# Op_Amp_VU_Meter_3_Led.net
KiCad netlist of a schematic drawn in EAGLE
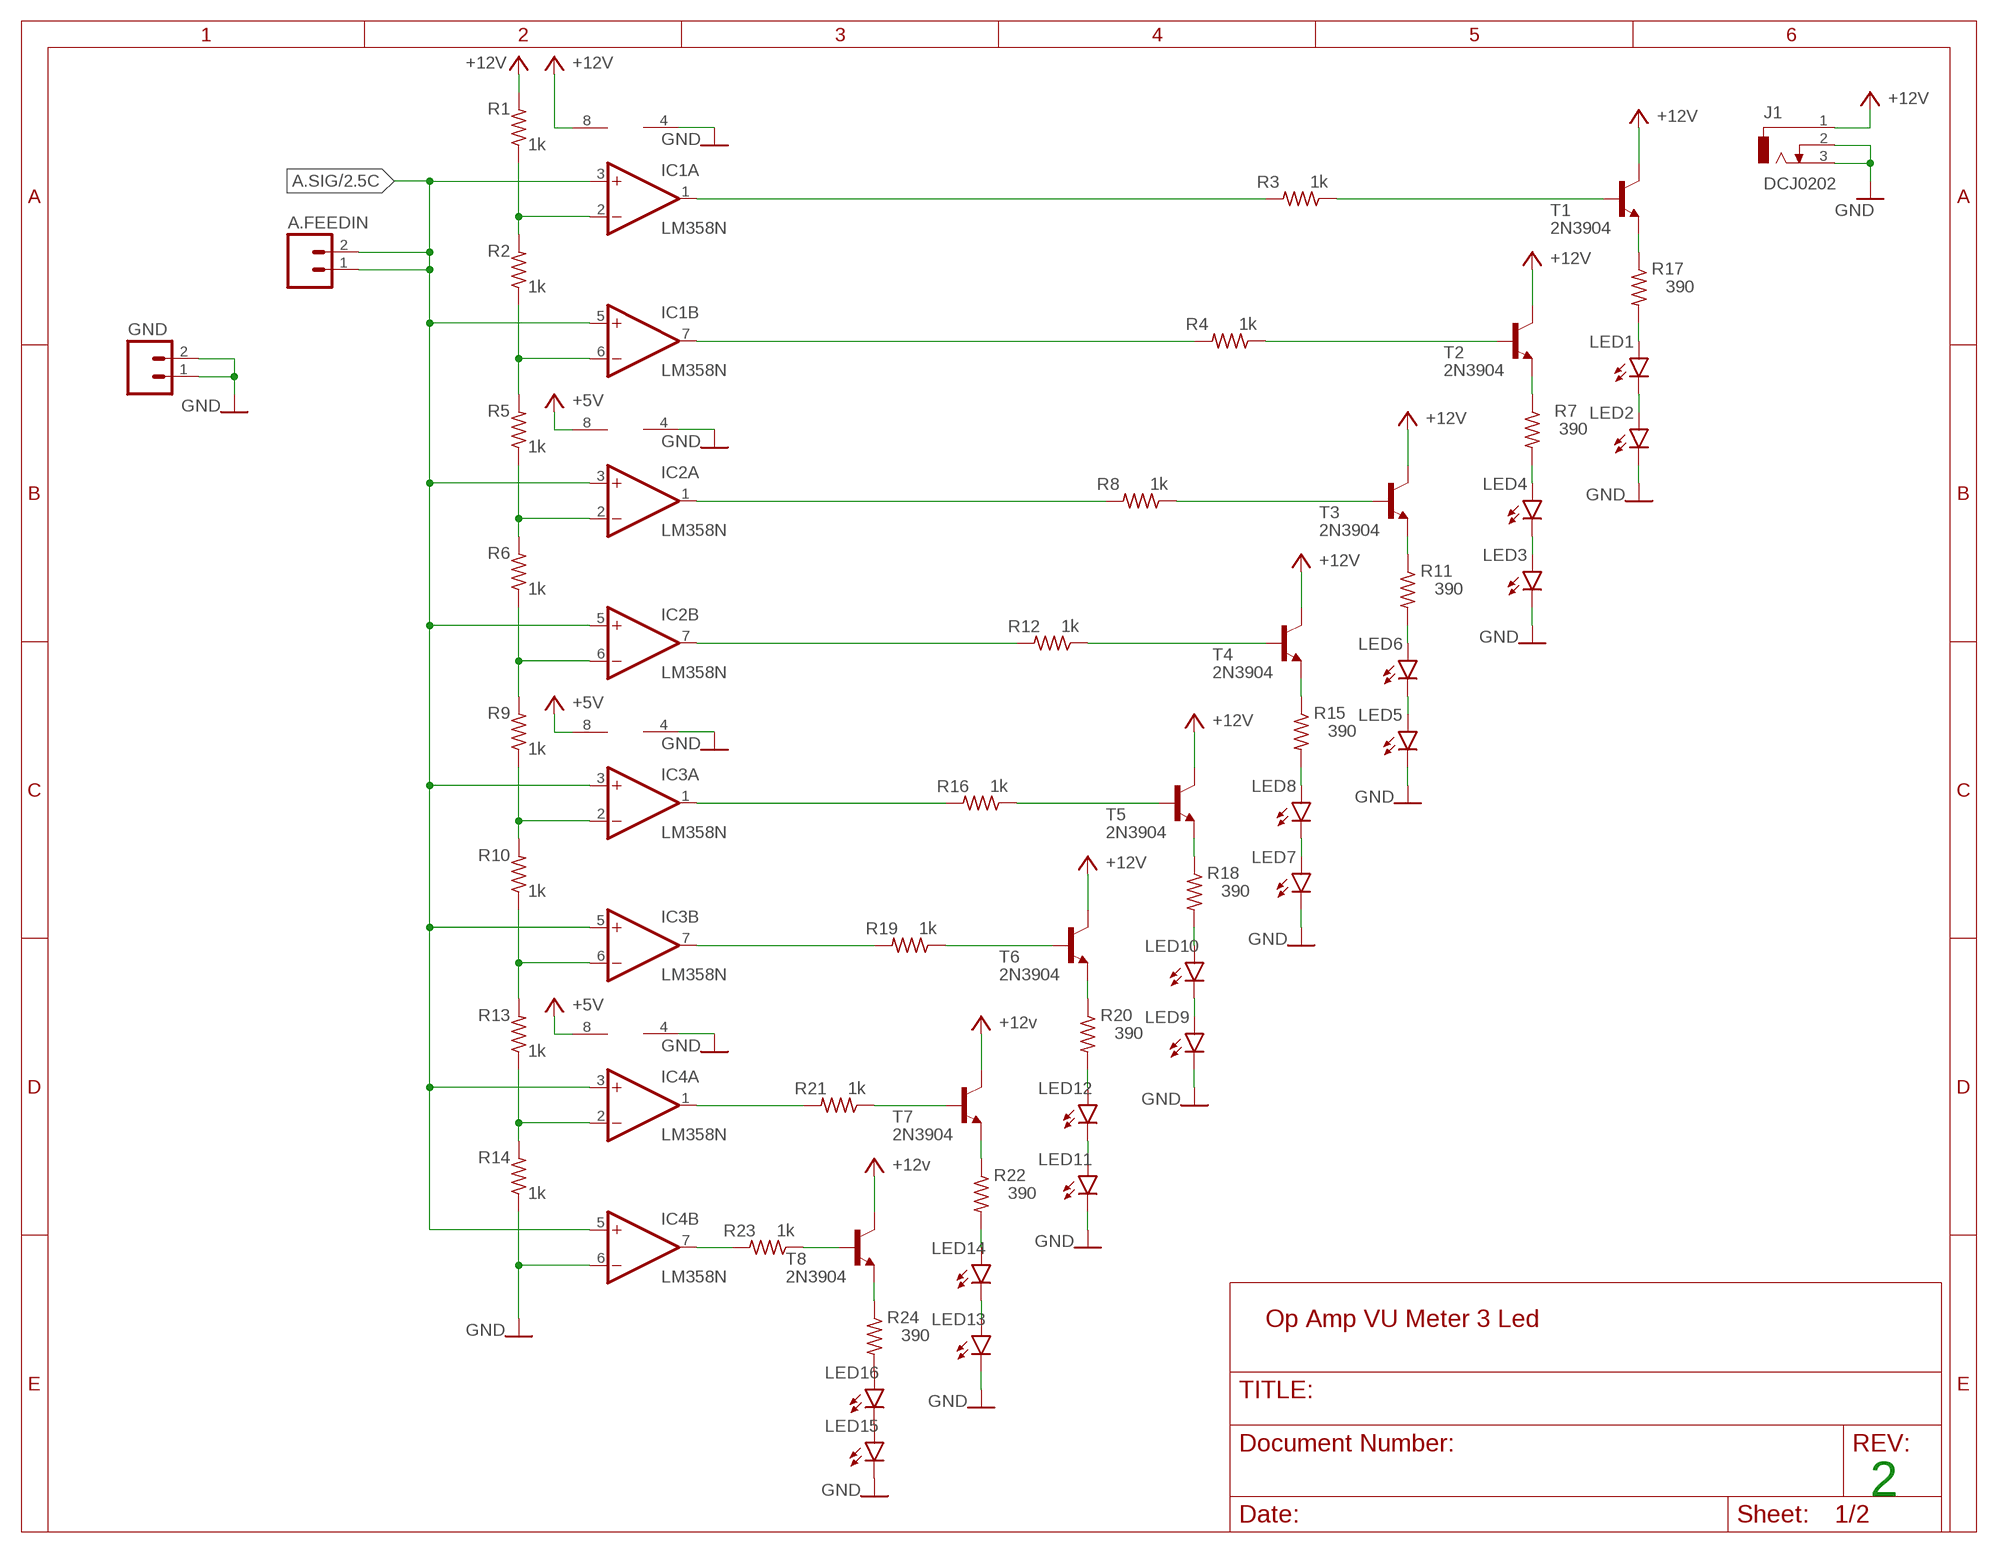
[diagram p0: schematic, sheet 1]
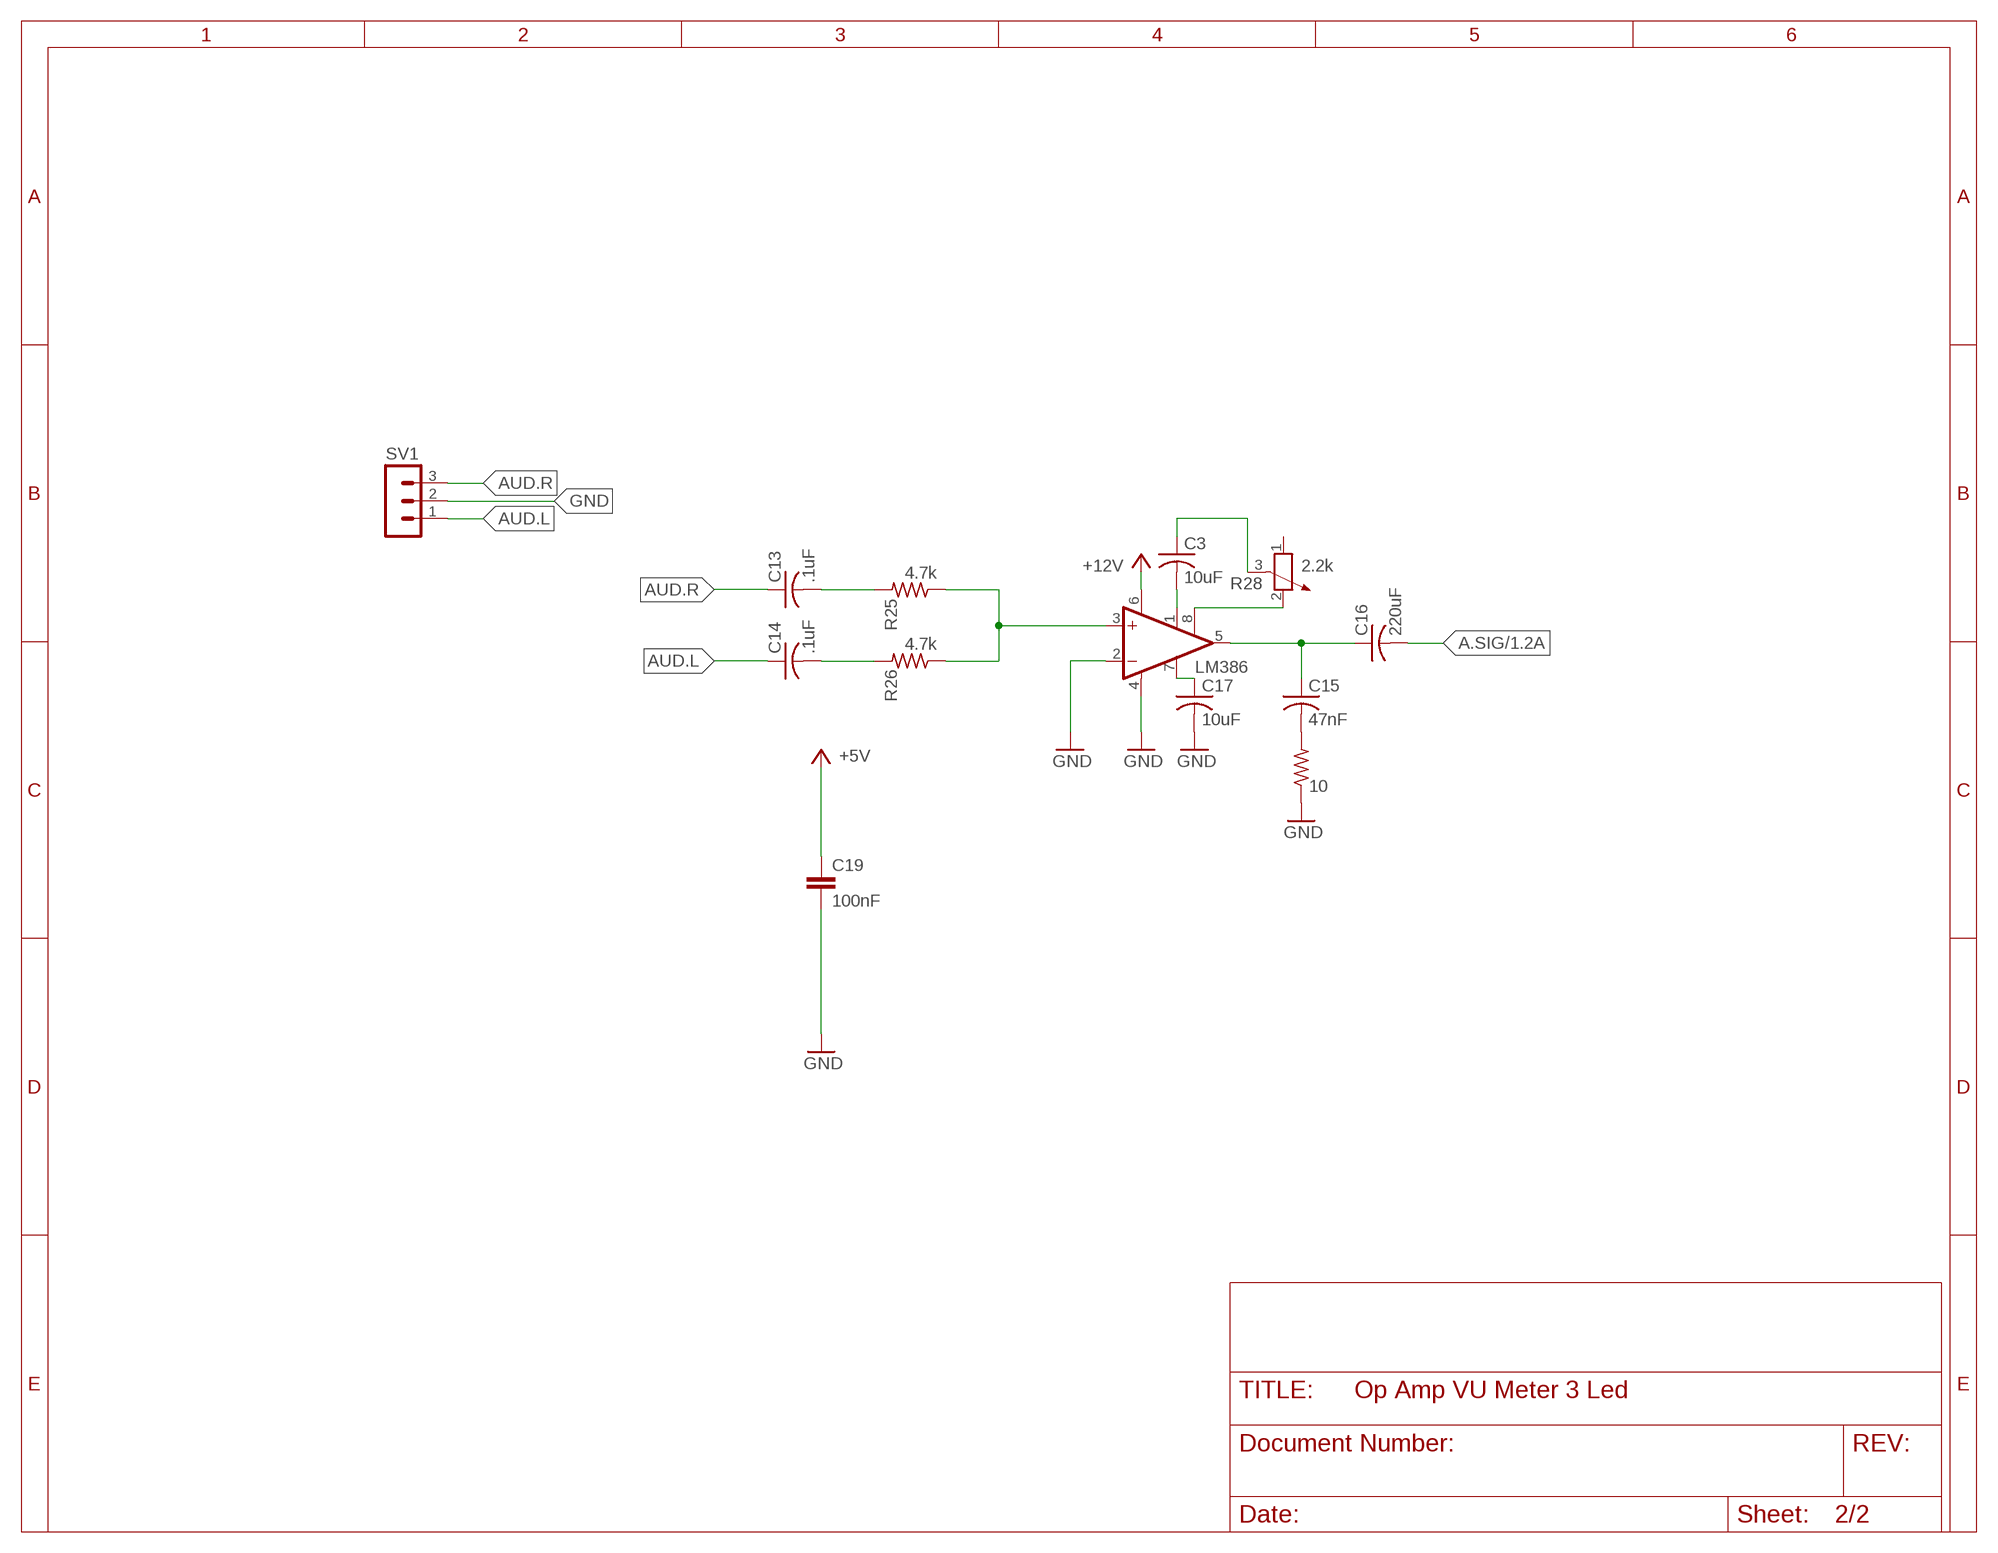
[diagram p1: schematic, sheet 2]

(export (version "E")
  (design (tool "Eeschema 10.0.6"))
  (components
    (comp (ref "C3")
      (value "10uF")
      (footprint "eagle-import:C050-024X044")
      (libsource (lib "eagle-import") (part "C-US050-024X044"))
    )
    (comp (ref "C13")
      (value ".1uF")
      (footprint "eagle-import:C050-024X044")
      (libsource (lib "eagle-import") (part "C-US050-024X044"))
    )
    (comp (ref "C14")
      (value ".1uF")
      (footprint "eagle-import:C050-024X044")
      (libsource (lib "eagle-import") (part "C-US050-024X044"))
    )
    (comp (ref "C15")
      (value "47nF")
      (footprint "eagle-import:C050-024X044")
      (libsource (lib "eagle-import") (part "C-US050-024X044"))
    )
    (comp (ref "C16")
      (value "220uF")
      (footprint "eagle-import:C050-024X044")
      (libsource (lib "eagle-import") (part "C-US050-024X044"))
    )
    (comp (ref "C17")
      (value "10uF")
      (footprint "eagle-import:C050-024X044")
      (libsource (lib "eagle-import") (part "C-US050-024X044"))
    )
    (comp (ref "C19")
      (value "100nF")
      (footprint "eagle-import:C025-025X050")
      (libsource (lib "eagle-import") (part "C-EU025-025X050"))
    )
    (comp (ref "LM386")
      (value "LM386N-1")
      (footprint "eagle-import:DIL08")
      (libsource (lib "eagle-import") (part "LM386?-N1"))
    )
    (comp (ref "R25")
      (value "4.7k")
      (footprint "eagle-import:0207_12")
      (libsource (lib "eagle-import") (part "R-US_0207/12"))
    )
    (comp (ref "R26")
      (value "4.7k")
      (footprint "eagle-import:0207_12")
      (libsource (lib "eagle-import") (part "R-US_0207/12"))
    )
    (comp (ref "R27")
      (value "10")
      (footprint "eagle-import:0207_12")
      (libsource (lib "eagle-import") (part "R-US_0207/12"))
    )
    (comp (ref "R28")
      (value "2.2k")
      (footprint "eagle-import:PT-10S")
      (libsource (lib "eagle-import") (part "POTENTIOMETER_PT-10S"))
    )
    (comp (ref "SV1")
      (value "MA03-1")
      (footprint "eagle-import:MA03-1")
      (libsource (lib "eagle-import") (part "MA03-1"))
    )
    (comp (ref "A.FEEDIN")
      (value "MA02")
      (footprint "eagle-import:02PA")
      (libsource (lib "eagle-import") (part "MA02"))
    )
    (comp (ref "GND")
      (value "MA02")
      (footprint "eagle-import:02PA")
      (libsource (lib "eagle-import") (part "MA02"))
    )
    (comp (ref "IC1")
      (value "LM358N")
      (footprint "eagle-import:DIL08")
      (libsource (lib "eagle-import") (part "LM358N"))
    )
    (comp (ref "IC2")
      (value "LM358N")
      (footprint "eagle-import:DIL08")
      (libsource (lib "eagle-import") (part "LM358N"))
    )
    (comp (ref "IC3")
      (value "LM358N")
      (footprint "eagle-import:DIL08")
      (libsource (lib "eagle-import") (part "LM358N"))
    )
    (comp (ref "IC4")
      (value "LM358N")
      (footprint "eagle-import:DIL08")
      (libsource (lib "eagle-import") (part "LM358N"))
    )
    (comp (ref "J1")
      (value "DCJ0202")
      (footprint "eagle-import:DCJ0202")
      (libsource (lib "eagle-import") (part "DCJ0202"))
    )
    (comp (ref "LED1")
      (value "LED5MM")
      (footprint "eagle-import:LED5MM")
      (libsource (lib "eagle-import") (part "LED5MM"))
    )
    (comp (ref "LED2")
      (value "LED5MM")
      (footprint "eagle-import:LED5MM")
      (libsource (lib "eagle-import") (part "LED5MM"))
    )
    (comp (ref "LED3")
      (value "LED5MM")
      (footprint "eagle-import:LED5MM")
      (libsource (lib "eagle-import") (part "LED5MM"))
    )
    (comp (ref "LED4")
      (value "LED5MM")
      (footprint "eagle-import:LED5MM")
      (libsource (lib "eagle-import") (part "LED5MM"))
    )
    (comp (ref "LED5")
      (value "LED5MM")
      (footprint "eagle-import:LED5MM")
      (libsource (lib "eagle-import") (part "LED5MM"))
    )
    (comp (ref "LED6")
      (value "LED5MM")
      (footprint "eagle-import:LED5MM")
      (libsource (lib "eagle-import") (part "LED5MM"))
    )
    (comp (ref "LED7")
      (value "LED5MM")
      (footprint "eagle-import:LED5MM")
      (libsource (lib "eagle-import") (part "LED5MM"))
    )
    (comp (ref "LED8")
      (value "LED5MM")
      (footprint "eagle-import:LED5MM")
      (libsource (lib "eagle-import") (part "LED5MM"))
    )
    (comp (ref "LED9")
      (value "LED5MM")
      (footprint "eagle-import:LED5MM")
      (libsource (lib "eagle-import") (part "LED5MM"))
    )
    (comp (ref "LED10")
      (value "LED5MM")
      (footprint "eagle-import:LED5MM")
      (libsource (lib "eagle-import") (part "LED5MM"))
    )
    (comp (ref "LED11")
      (value "LED5MM")
      (footprint "eagle-import:LED5MM")
      (libsource (lib "eagle-import") (part "LED5MM"))
    )
    (comp (ref "LED12")
      (value "LED5MM")
      (footprint "eagle-import:LED5MM")
      (libsource (lib "eagle-import") (part "LED5MM"))
    )
    (comp (ref "LED13")
      (value "LED5MM")
      (footprint "eagle-import:LED5MM")
      (libsource (lib "eagle-import") (part "LED5MM"))
    )
    (comp (ref "LED14")
      (value "LED5MM")
      (footprint "eagle-import:LED5MM")
      (libsource (lib "eagle-import") (part "LED5MM"))
    )
    (comp (ref "LED15")
      (value "LED5MM")
      (footprint "eagle-import:LED5MM")
      (libsource (lib "eagle-import") (part "LED5MM"))
    )
    (comp (ref "LED16")
      (value "LED5MM")
      (footprint "eagle-import:LED5MM")
      (libsource (lib "eagle-import") (part "LED5MM"))
    )
    (comp (ref "R1")
      (value "1k")
      (footprint "eagle-import:0207_12")
      (libsource (lib "eagle-import") (part "R-US_0207/12"))
    )
    (comp (ref "R2")
      (value "1k")
      (footprint "eagle-import:0207_12")
      (libsource (lib "eagle-import") (part "R-US_0207/12"))
    )
    (comp (ref "R3")
      (value "1k")
      (footprint "eagle-import:0207_12")
      (libsource (lib "eagle-import") (part "R-US_0207/12"))
    )
    (comp (ref "R4")
      (value "1k")
      (footprint "eagle-import:0207_12")
      (libsource (lib "eagle-import") (part "R-US_0207/12"))
    )
    (comp (ref "R5")
      (value "1k")
      (footprint "eagle-import:0207_12")
      (libsource (lib "eagle-import") (part "R-US_0207/12"))
    )
    (comp (ref "R6")
      (value "1k")
      (footprint "eagle-import:0207_12")
      (libsource (lib "eagle-import") (part "R-US_0207/12"))
    )
    (comp (ref "R7")
      (value "390")
      (footprint "eagle-import:0207_12")
      (libsource (lib "eagle-import") (part "R-US_0207/12"))
    )
    (comp (ref "R8")
      (value "1k")
      (footprint "eagle-import:0207_12")
      (libsource (lib "eagle-import") (part "R-US_0207/12"))
    )
    (comp (ref "R9")
      (value "1k")
      (footprint "eagle-import:0207_12")
      (libsource (lib "eagle-import") (part "R-US_0207/12"))
    )
    (comp (ref "R10")
      (value "1k")
      (footprint "eagle-import:0207_12")
      (libsource (lib "eagle-import") (part "R-US_0207/12"))
    )
    (comp (ref "R11")
      (value "390")
      (footprint "eagle-import:0207_12")
      (libsource (lib "eagle-import") (part "R-US_0207/12"))
    )
    (comp (ref "R12")
      (value "1k")
      (footprint "eagle-import:0207_12")
      (libsource (lib "eagle-import") (part "R-US_0207/12"))
    )
    (comp (ref "R13")
      (value "1k")
      (footprint "eagle-import:0207_12")
      (libsource (lib "eagle-import") (part "R-US_0207/12"))
    )
    (comp (ref "R14")
      (value "1k")
      (footprint "eagle-import:0207_12")
      (libsource (lib "eagle-import") (part "R-US_0207/12"))
    )
    (comp (ref "R15")
      (value "390")
      (footprint "eagle-import:0207_12")
      (libsource (lib "eagle-import") (part "R-US_0207/12"))
    )
    (comp (ref "R16")
      (value "1k")
      (footprint "eagle-import:0207_12")
      (libsource (lib "eagle-import") (part "R-US_0207/12"))
    )
    (comp (ref "R17")
      (value "390")
      (footprint "eagle-import:0207_12")
      (libsource (lib "eagle-import") (part "R-US_0207/12"))
    )
    (comp (ref "R18")
      (value "390")
      (footprint "eagle-import:0207_12")
      (libsource (lib "eagle-import") (part "R-US_0207/12"))
    )
    (comp (ref "R19")
      (value "1k")
      (footprint "eagle-import:0207_12")
      (libsource (lib "eagle-import") (part "R-US_0207/12"))
    )
    (comp (ref "R20")
      (value "390")
      (footprint "eagle-import:0207_12")
      (libsource (lib "eagle-import") (part "R-US_0207/12"))
    )
    (comp (ref "R21")
      (value "1k")
      (footprint "eagle-import:0207_12")
      (libsource (lib "eagle-import") (part "R-US_0207/12"))
    )
    (comp (ref "R22")
      (value "390")
      (footprint "eagle-import:0207_12")
      (libsource (lib "eagle-import") (part "R-US_0207/12"))
    )
    (comp (ref "R23")
      (value "1k")
      (footprint "eagle-import:0207_12")
      (libsource (lib "eagle-import") (part "R-US_0207/12"))
    )
    (comp (ref "R24")
      (value "390")
      (footprint "eagle-import:0207_12")
      (libsource (lib "eagle-import") (part "R-US_0207/12"))
    )
    (comp (ref "T1")
      (value "2N3904")
      (footprint "eagle-import:TO92")
      (libsource (lib "eagle-import") (part "2N3904"))
    )
    (comp (ref "T2")
      (value "2N3904")
      (footprint "eagle-import:TO92")
      (libsource (lib "eagle-import") (part "2N3904"))
    )
    (comp (ref "T3")
      (value "2N3904")
      (footprint "eagle-import:TO92")
      (libsource (lib "eagle-import") (part "2N3904"))
    )
    (comp (ref "T4")
      (value "2N3904")
      (footprint "eagle-import:TO92")
      (libsource (lib "eagle-import") (part "2N3904"))
    )
    (comp (ref "T5")
      (value "2N3904")
      (footprint "eagle-import:TO92")
      (libsource (lib "eagle-import") (part "2N3904"))
    )
    (comp (ref "T6")
      (value "2N3904")
      (footprint "eagle-import:TO92")
      (libsource (lib "eagle-import") (part "2N3904"))
    )
    (comp (ref "T7")
      (value "2N3904")
      (footprint "eagle-import:TO92")
      (libsource (lib "eagle-import") (part "2N3904"))
    )
    (comp (ref "T8")
      (value "2N3904")
      (footprint "eagle-import:TO92")
      (libsource (lib "eagle-import") (part "2N3904"))
    )
  )
  (nets
    (net (code "1") (name "+5V") (class "Default")
      (node (ref "C19") (pin "1") (pinfunction "1_1") (pintype "passive"))
      (node (ref "IC1") (pin "8") (pinfunction "V+_8") (pintype "power_in"))
      (node (ref "IC2") (pin "8") (pinfunction "V+_8") (pintype "power_in"))
      (node (ref "IC3") (pin "8") (pinfunction "V+_8") (pintype "power_in"))
      (node (ref "IC4") (pin "8") (pinfunction "V+_8") (pintype "power_in"))
      (node (ref "J1") (pin "1") (pinfunction "1_1") (pintype "passive"))
      (node (ref "LM386") (pin "6") (pinfunction "VS_6") (pintype "power_in"))
      (node (ref "R1") (pin "2") (pinfunction "2_2") (pintype "passive"))
      (node (ref "T1") (pin "1") (pinfunction "C_1") (pintype "passive"))
      (node (ref "T2") (pin "1") (pinfunction "C_1") (pintype "passive"))
      (node (ref "T3") (pin "1") (pinfunction "C_1") (pintype "passive"))
      (node (ref "T4") (pin "1") (pinfunction "C_1") (pintype "passive"))
      (node (ref "T5") (pin "1") (pinfunction "C_1") (pintype "passive"))
      (node (ref "T6") (pin "1") (pinfunction "C_1") (pintype "passive"))
      (node (ref "T7") (pin "1") (pinfunction "C_1") (pintype "passive"))
      (node (ref "T8") (pin "1") (pinfunction "C_1") (pintype "passive"))
    )
    (net (code "2") (name "A.SIG") (class "Default")
      (node (ref "A.FEEDIN") (pin "1") (pinfunction "1_1") (pintype "passive"))
      (node (ref "A.FEEDIN") (pin "2") (pinfunction "2_2") (pintype "passive"))
      (node (ref "C16") (pin "2") (pinfunction "2_2") (pintype "passive"))
      (node (ref "IC1") (pin "3") (pinfunction "+IN_3") (pintype "input"))
      (node (ref "IC1") (pin "5") (pinfunction "+IN_5") (pintype "input"))
      (node (ref "IC2") (pin "3") (pinfunction "+IN_3") (pintype "input"))
      (node (ref "IC2") (pin "5") (pinfunction "+IN_5") (pintype "input"))
      (node (ref "IC3") (pin "3") (pinfunction "+IN_3") (pintype "input"))
      (node (ref "IC3") (pin "5") (pinfunction "+IN_5") (pintype "input"))
      (node (ref "IC4") (pin "3") (pinfunction "+IN_3") (pintype "input"))
      (node (ref "IC4") (pin "5") (pinfunction "+IN_5") (pintype "input"))
    )
    (net (code "3") (name "AUD.L") (class "Default")
      (node (ref "C14") (pin "1") (pinfunction "1_1") (pintype "passive"))
      (node (ref "SV1") (pin "1") (pinfunction "1_1") (pintype "passive"))
    )
    (net (code "4") (name "AUD.R") (class "Default")
      (node (ref "C13") (pin "1") (pinfunction "1_1") (pintype "passive"))
      (node (ref "SV1") (pin "3") (pinfunction "3_3") (pintype "passive"))
    )
    (net (code "5") (name "GND") (class "Default")
      (node (ref "C17") (pin "2") (pinfunction "2_2") (pintype "passive"))
      (node (ref "C19") (pin "2") (pinfunction "2_2") (pintype "passive"))
      (node (ref "GND") (pin "1") (pinfunction "1_1") (pintype "passive"))
      (node (ref "GND") (pin "2") (pinfunction "2_2") (pintype "passive"))
      (node (ref "IC1") (pin "4") (pinfunction "V-_4") (pintype "power_in"))
      (node (ref "IC2") (pin "4") (pinfunction "V-_4") (pintype "power_in"))
      (node (ref "IC3") (pin "4") (pinfunction "V-_4") (pintype "power_in"))
      (node (ref "IC4") (pin "4") (pinfunction "V-_4") (pintype "power_in"))
      (node (ref "IC4") (pin "6") (pinfunction "-IN_6") (pintype "input"))
      (node (ref "J1") (pin "2") (pinfunction "2_2") (pintype "passive"))
      (node (ref "J1") (pin "3") (pinfunction "3_3") (pintype "passive"))
      (node (ref "LED11") (pin "K") (pinfunction "C_K") (pintype "passive"))
      (node (ref "LED13") (pin "K") (pinfunction "C_K") (pintype "passive"))
      (node (ref "LED15") (pin "K") (pinfunction "C_K") (pintype "passive"))
      (node (ref "LED2") (pin "K") (pinfunction "C_K") (pintype "passive"))
      (node (ref "LED3") (pin "K") (pinfunction "C_K") (pintype "passive"))
      (node (ref "LED5") (pin "K") (pinfunction "C_K") (pintype "passive"))
      (node (ref "LED7") (pin "K") (pinfunction "C_K") (pintype "passive"))
      (node (ref "LED9") (pin "K") (pinfunction "C_K") (pintype "passive"))
      (node (ref "LM386") (pin "2") (pinfunction "-IN_2") (pintype "input"))
      (node (ref "LM386") (pin "4") (pinfunction "GND_4") (pintype "power_in"))
      (node (ref "R14") (pin "1") (pinfunction "1_1") (pintype "passive"))
      (node (ref "R27") (pin "1") (pinfunction "1_1") (pintype "passive"))
      (node (ref "SV1") (pin "2") (pinfunction "2_2") (pintype "passive"))
    )
    (net (code "6") (name "Net-(C3-Pad1)") (class "Default")
      (node (ref "C3") (pin "1") (pinfunction "1_1") (pintype "passive"))
      (node (ref "R28") (pin "3") (pinfunction "3_3") (pintype "passive"))
    )
    (net (code "7") (name "Net-(C3-Pad2)") (class "Default")
      (node (ref "C3") (pin "2") (pinfunction "2_2") (pintype "passive"))
      (node (ref "LM386") (pin "1") (pinfunction "GAIN_1") (pintype "passive"))
    )
    (net (code "8") (name "Net-(C13-Pad2)") (class "Default")
      (node (ref "C13") (pin "2") (pinfunction "2_2") (pintype "passive"))
      (node (ref "R25") (pin "2") (pinfunction "2_2") (pintype "passive"))
    )
    (net (code "9") (name "Net-(C14-Pad2)") (class "Default")
      (node (ref "C14") (pin "2") (pinfunction "2_2") (pintype "passive"))
      (node (ref "R26") (pin "2") (pinfunction "2_2") (pintype "passive"))
    )
    (net (code "10") (name "Net-(C15-Pad2)") (class "Default")
      (node (ref "C15") (pin "2") (pinfunction "2_2") (pintype "passive"))
      (node (ref "R27") (pin "2") (pinfunction "2_2") (pintype "passive"))
    )
    (net (code "11") (name "Net-(IC1A--IN)") (class "Default")
      (node (ref "IC1") (pin "2") (pinfunction "-IN_2") (pintype "input"))
      (node (ref "R1") (pin "1") (pinfunction "1_1") (pintype "passive"))
      (node (ref "R2") (pin "2") (pinfunction "2_2") (pintype "passive"))
    )
    (net (code "12") (name "Net-(IC1A-OUT)") (class "Default")
      (node (ref "IC1") (pin "1") (pinfunction "OUT_1") (pintype "output"))
      (node (ref "R3") (pin "2") (pinfunction "2_2") (pintype "passive"))
    )
    (net (code "13") (name "Net-(IC1B--IN)") (class "Default")
      (node (ref "IC1") (pin "6") (pinfunction "-IN_6") (pintype "input"))
      (node (ref "R2") (pin "1") (pinfunction "1_1") (pintype "passive"))
      (node (ref "R5") (pin "2") (pinfunction "2_2") (pintype "passive"))
    )
    (net (code "14") (name "Net-(IC1B-OUT)") (class "Default")
      (node (ref "IC1") (pin "7") (pinfunction "OUT_7") (pintype "output"))
      (node (ref "R4") (pin "2") (pinfunction "2_2") (pintype "passive"))
    )
    (net (code "15") (name "Net-(IC2A--IN)") (class "Default")
      (node (ref "IC2") (pin "2") (pinfunction "-IN_2") (pintype "input"))
      (node (ref "R5") (pin "1") (pinfunction "1_1") (pintype "passive"))
      (node (ref "R6") (pin "2") (pinfunction "2_2") (pintype "passive"))
    )
    (net (code "16") (name "Net-(IC2A-OUT)") (class "Default")
      (node (ref "IC2") (pin "1") (pinfunction "OUT_1") (pintype "output"))
      (node (ref "R8") (pin "2") (pinfunction "2_2") (pintype "passive"))
    )
    (net (code "17") (name "Net-(IC2B--IN)") (class "Default")
      (node (ref "IC2") (pin "6") (pinfunction "-IN_6") (pintype "input"))
      (node (ref "R6") (pin "1") (pinfunction "1_1") (pintype "passive"))
      (node (ref "R9") (pin "2") (pinfunction "2_2") (pintype "passive"))
    )
    (net (code "18") (name "Net-(IC2B-OUT)") (class "Default")
      (node (ref "IC2") (pin "7") (pinfunction "OUT_7") (pintype "output"))
      (node (ref "R12") (pin "2") (pinfunction "2_2") (pintype "passive"))
    )
    (net (code "19") (name "Net-(IC3A--IN)") (class "Default")
      (node (ref "IC3") (pin "2") (pinfunction "-IN_2") (pintype "input"))
      (node (ref "R10") (pin "2") (pinfunction "2_2") (pintype "passive"))
      (node (ref "R9") (pin "1") (pinfunction "1_1") (pintype "passive"))
    )
    (net (code "20") (name "Net-(IC3A-OUT)") (class "Default")
      (node (ref "IC3") (pin "1") (pinfunction "OUT_1") (pintype "output"))
      (node (ref "R16") (pin "2") (pinfunction "2_2") (pintype "passive"))
    )
    (net (code "21") (name "Net-(IC3B--IN)") (class "Default")
      (node (ref "IC3") (pin "6") (pinfunction "-IN_6") (pintype "input"))
      (node (ref "R10") (pin "1") (pinfunction "1_1") (pintype "passive"))
      (node (ref "R13") (pin "2") (pinfunction "2_2") (pintype "passive"))
    )
    (net (code "22") (name "Net-(IC3B-OUT)") (class "Default")
      (node (ref "IC3") (pin "7") (pinfunction "OUT_7") (pintype "output"))
      (node (ref "R19") (pin "2") (pinfunction "2_2") (pintype "passive"))
    )
    (net (code "23") (name "Net-(IC4A--IN)") (class "Default")
      (node (ref "IC4") (pin "2") (pinfunction "-IN_2") (pintype "input"))
      (node (ref "R13") (pin "1") (pinfunction "1_1") (pintype "passive"))
      (node (ref "R14") (pin "2") (pinfunction "2_2") (pintype "passive"))
    )
    (net (code "24") (name "Net-(IC4A-OUT)") (class "Default")
      (node (ref "IC4") (pin "1") (pinfunction "OUT_1") (pintype "output"))
      (node (ref "R21") (pin "2") (pinfunction "2_2") (pintype "passive"))
    )
    (net (code "25") (name "Net-(IC4B-OUT)") (class "Default")
      (node (ref "IC4") (pin "7") (pinfunction "OUT_7") (pintype "output"))
      (node (ref "R23") (pin "2") (pinfunction "2_2") (pintype "passive"))
    )
    (net (code "26") (name "Net-(LED1-C)") (class "Default")
      (node (ref "LED1") (pin "K") (pinfunction "C_K") (pintype "passive"))
      (node (ref "LED2") (pin "A") (pinfunction "A_A") (pintype "passive"))
    )
    (net (code "27") (name "Net-(LED1-PadA)") (class "Default")
      (node (ref "LED1") (pin "A") (pinfunction "A_A") (pintype "passive"))
      (node (ref "R17") (pin "2") (pinfunction "2_2") (pintype "passive"))
    )
    (net (code "28") (name "Net-(LED4-C)") (class "Default")
      (node (ref "LED3") (pin "A") (pinfunction "A_A") (pintype "passive"))
      (node (ref "LED4") (pin "K") (pinfunction "C_K") (pintype "passive"))
    )
    (net (code "29") (name "Net-(LED4-PadA)") (class "Default")
      (node (ref "LED4") (pin "A") (pinfunction "A_A") (pintype "passive"))
      (node (ref "R7") (pin "2") (pinfunction "2_2") (pintype "passive"))
    )
    (net (code "30") (name "Net-(LED6-C)") (class "Default")
      (node (ref "LED5") (pin "A") (pinfunction "A_A") (pintype "passive"))
      (node (ref "LED6") (pin "K") (pinfunction "C_K") (pintype "passive"))
    )
    (net (code "31") (name "Net-(LED6-PadA)") (class "Default")
      (node (ref "LED6") (pin "A") (pinfunction "A_A") (pintype "passive"))
      (node (ref "R11") (pin "2") (pinfunction "2_2") (pintype "passive"))
    )
    (net (code "32") (name "Net-(LED8-C)") (class "Default")
      (node (ref "LED7") (pin "A") (pinfunction "A_A") (pintype "passive"))
      (node (ref "LED8") (pin "K") (pinfunction "C_K") (pintype "passive"))
    )
    (net (code "33") (name "Net-(LED8-PadA)") (class "Default")
      (node (ref "LED8") (pin "A") (pinfunction "A_A") (pintype "passive"))
      (node (ref "R15") (pin "2") (pinfunction "2_2") (pintype "passive"))
    )
    (net (code "34") (name "Net-(LED10-C)") (class "Default")
      (node (ref "LED10") (pin "K") (pinfunction "C_K") (pintype "passive"))
      (node (ref "LED9") (pin "A") (pinfunction "A_A") (pintype "passive"))
    )
    (net (code "35") (name "Net-(LED10-PadA)") (class "Default")
      (node (ref "LED10") (pin "A") (pinfunction "A_A") (pintype "passive"))
      (node (ref "R18") (pin "2") (pinfunction "2_2") (pintype "passive"))
    )
    (net (code "36") (name "Net-(LED12-C)") (class "Default")
      (node (ref "LED11") (pin "A") (pinfunction "A_A") (pintype "passive"))
      (node (ref "LED12") (pin "K") (pinfunction "C_K") (pintype "passive"))
    )
    (net (code "37") (name "Net-(LED12-PadA)") (class "Default")
      (node (ref "LED12") (pin "A") (pinfunction "A_A") (pintype "passive"))
      (node (ref "R20") (pin "2") (pinfunction "2_2") (pintype "passive"))
    )
    (net (code "38") (name "Net-(LED14-C)") (class "Default")
      (node (ref "LED13") (pin "A") (pinfunction "A_A") (pintype "passive"))
      (node (ref "LED14") (pin "K") (pinfunction "C_K") (pintype "passive"))
    )
    (net (code "39") (name "Net-(LED14-PadA)") (class "Default")
      (node (ref "LED14") (pin "A") (pinfunction "A_A") (pintype "passive"))
      (node (ref "R22") (pin "2") (pinfunction "2_2") (pintype "passive"))
    )
    (net (code "40") (name "Net-(LED16-C)") (class "Default")
      (node (ref "LED15") (pin "A") (pinfunction "A_A") (pintype "passive"))
      (node (ref "LED16") (pin "K") (pinfunction "C_K") (pintype "passive"))
    )
    (net (code "41") (name "Net-(LED16-PadA)") (class "Default")
      (node (ref "LED16") (pin "A") (pinfunction "A_A") (pintype "passive"))
      (node (ref "R24") (pin "2") (pinfunction "2_2") (pintype "passive"))
    )
    (net (code "42") (name "Net-(LM386-+IN)") (class "Default")
      (node (ref "LM386") (pin "3") (pinfunction "+IN_3") (pintype "input"))
      (node (ref "R25") (pin "1") (pinfunction "1_1") (pintype "passive"))
      (node (ref "R26") (pin "1") (pinfunction "1_1") (pintype "passive"))
    )
    (net (code "43") (name "Net-(LM386-BYPASS)") (class "Default")
      (node (ref "C17") (pin "1") (pinfunction "1_1") (pintype "passive"))
      (node (ref "LM386") (pin "7") (pinfunction "BYPASS_7") (pintype "passive"))
    )
    (net (code "44") (name "Net-(LM386-GAIN-Pad8)") (class "Default")
      (node (ref "LM386") (pin "8") (pinfunction "GAIN_8") (pintype "passive"))
      (node (ref "R28") (pin "2") (pinfunction "2_2") (pintype "passive"))
    )
    (net (code "45") (name "Net-(LM386-OUT)") (class "Default")
      (node (ref "C15") (pin "1") (pinfunction "1_1") (pintype "passive"))
      (node (ref "C16") (pin "1") (pinfunction "1_1") (pintype "passive"))
      (node (ref "LM386") (pin "5") (pinfunction "OUT_5") (pintype "output"))
    )
    (net (code "46") (name "Net-(T1-B)") (class "Default")
      (node (ref "R3") (pin "1") (pinfunction "1_1") (pintype "passive"))
      (node (ref "T1") (pin "2") (pinfunction "B_2") (pintype "passive"))
    )
    (net (code "47") (name "Net-(T1-E)") (class "Default")
      (node (ref "R17") (pin "1") (pinfunction "1_1") (pintype "passive"))
      (node (ref "T1") (pin "3") (pinfunction "E_3") (pintype "passive"))
    )
    (net (code "48") (name "Net-(T2-B)") (class "Default")
      (node (ref "R4") (pin "1") (pinfunction "1_1") (pintype "passive"))
      (node (ref "T2") (pin "2") (pinfunction "B_2") (pintype "passive"))
    )
    (net (code "49") (name "Net-(T2-E)") (class "Default")
      (node (ref "R7") (pin "1") (pinfunction "1_1") (pintype "passive"))
      (node (ref "T2") (pin "3") (pinfunction "E_3") (pintype "passive"))
    )
    (net (code "50") (name "Net-(T3-B)") (class "Default")
      (node (ref "R8") (pin "1") (pinfunction "1_1") (pintype "passive"))
      (node (ref "T3") (pin "2") (pinfunction "B_2") (pintype "passive"))
    )
    (net (code "51") (name "Net-(T3-E)") (class "Default")
      (node (ref "R11") (pin "1") (pinfunction "1_1") (pintype "passive"))
      (node (ref "T3") (pin "3") (pinfunction "E_3") (pintype "passive"))
    )
    (net (code "52") (name "Net-(T4-B)") (class "Default")
      (node (ref "R12") (pin "1") (pinfunction "1_1") (pintype "passive"))
      (node (ref "T4") (pin "2") (pinfunction "B_2") (pintype "passive"))
    )
    (net (code "53") (name "Net-(T4-E)") (class "Default")
      (node (ref "R15") (pin "1") (pinfunction "1_1") (pintype "passive"))
      (node (ref "T4") (pin "3") (pinfunction "E_3") (pintype "passive"))
    )
    (net (code "54") (name "Net-(T5-B)") (class "Default")
      (node (ref "R16") (pin "1") (pinfunction "1_1") (pintype "passive"))
      (node (ref "T5") (pin "2") (pinfunction "B_2") (pintype "passive"))
    )
    (net (code "55") (name "Net-(T5-E)") (class "Default")
      (node (ref "R18") (pin "1") (pinfunction "1_1") (pintype "passive"))
      (node (ref "T5") (pin "3") (pinfunction "E_3") (pintype "passive"))
    )
    (net (code "56") (name "Net-(T6-B)") (class "Default")
      (node (ref "R19") (pin "1") (pinfunction "1_1") (pintype "passive"))
      (node (ref "T6") (pin "2") (pinfunction "B_2") (pintype "passive"))
    )
    (net (code "57") (name "Net-(T6-E)") (class "Default")
      (node (ref "R20") (pin "1") (pinfunction "1_1") (pintype "passive"))
      (node (ref "T6") (pin "3") (pinfunction "E_3") (pintype "passive"))
    )
    (net (code "58") (name "Net-(T7-B)") (class "Default")
      (node (ref "R21") (pin "1") (pinfunction "1_1") (pintype "passive"))
      (node (ref "T7") (pin "2") (pinfunction "B_2") (pintype "passive"))
    )
    (net (code "59") (name "Net-(T7-E)") (class "Default")
      (node (ref "R22") (pin "1") (pinfunction "1_1") (pintype "passive"))
      (node (ref "T7") (pin "3") (pinfunction "E_3") (pintype "passive"))
    )
    (net (code "60") (name "Net-(T8-B)") (class "Default")
      (node (ref "R23") (pin "1") (pinfunction "1_1") (pintype "passive"))
      (node (ref "T8") (pin "2") (pinfunction "B_2") (pintype "passive"))
    )
    (net (code "61") (name "Net-(T8-E)") (class "Default")
      (node (ref "R24") (pin "1") (pinfunction "1_1") (pintype "passive"))
      (node (ref "T8") (pin "3") (pinfunction "E_3") (pintype "passive"))
    )
    (net (code "62") (name "unconnected-(R28-Pad1)") (class "Default")
      (node (ref "R28") (pin "1") (pinfunction "1_1") (pintype "passive"))
    )
  )
)
